# heaters-connectors.net
KiCad netlist of a schematic drawn in Altium Designer
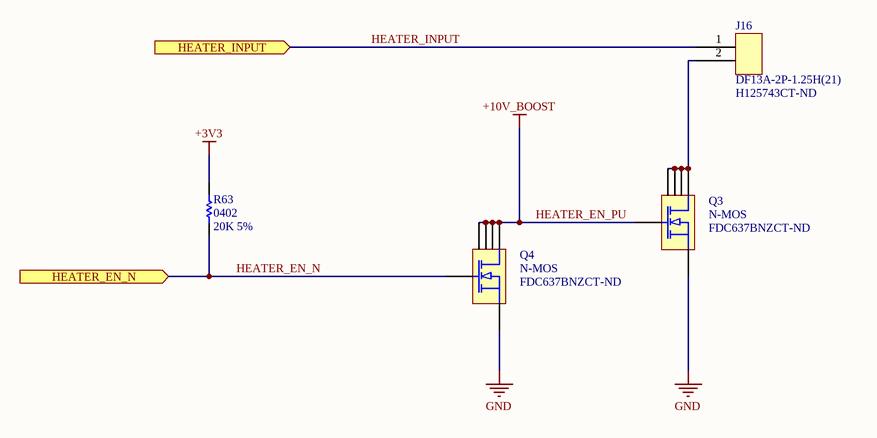
[diagram p0: heaters-connectors.SchDoc]

(export (version "E")
  (design (tool "Eeschema 10.0.6"))
  (components
    (comp (ref "J16")
      (value "DF13A-2P-1.25H(21)")
      (footprint "DF13A-2P-1.25H(21)")
      (description "2 pos DF13 right angle surface mount connector")
      (fields (field (name "SUPPLIER PART NUMBER 1") "H125743CT-ND"))
      (libsource (lib "DF13A-2P-1.25H(21)") (part "DF13A-2P-1.25H(21)"))
    )
    (comp (ref "Q3")
      (value "N-MOS")
      (footprint "SOT95P280X145-6N")
      (description "20V 6.2A, N-MOS, low gate on voltage")
      (fields (field (name "SUPPLIER PART NUMBER 1") "FDC637BNZCT-ND"))
      (libsource (lib "heron-general") (part "FDC637BNZCT-ND"))
    )
    (comp (ref "Q4")
      (value "N-MOS")
      (footprint "SOT95P280X145-6N")
      (description "20V 6.2A, N-MOS, low gate on voltage")
      (fields (field (name "SUPPLIER PART NUMBER 1") "FDC637BNZCT-ND"))
      (libsource (lib "heron-general") (part "FDC637BNZCT-ND"))
    )
    (comp (ref "R63")
      (value "0402")
      (footprint "RES0402R")
      (description "0402 resistor")
      (fields (field (name "ALTIUM_VALUE") "20K 5%"))
      (libsource (lib "RES0402") (part "RES0402"))
    )
  )
  (nets
    (net (code "1") (name "+3V3") (class "Default")
      (node (ref "R63") (pin "2") (pinfunction "2_2") (pintype "passive"))
    )
    (net (code "2") (name "+10V_BOOST") (class "Default")
      (node (ref "Q3") (pin "3") (pinfunction "G_3") (pintype "passive"))
      (node (ref "Q4") (pin "1") (pinfunction "D_1") (pintype "passive"))
      (node (ref "Q4") (pin "2") (pinfunction "D_2") (pintype "passive"))
      (node (ref "Q4") (pin "5") (pinfunction "D_5") (pintype "passive"))
      (node (ref "Q4") (pin "6") (pinfunction "D_6") (pintype "passive"))
    )
    (net (code "3") (name "/HEATER_EN_N") (class "Default")
      (node (ref "Q4") (pin "3") (pinfunction "G_3") (pintype "passive"))
      (node (ref "R63") (pin "1") (pinfunction "1_1") (pintype "passive"))
    )
    (net (code "4") (name "/HEATER_INPUT") (class "Default") (node (ref "J16") (pin "1") (pintype "passive")))
    (net (code "5") (name "GND") (class "Default")
      (node (ref "Q3") (pin "4") (pinfunction "S_4") (pintype "passive"))
      (node (ref "Q4") (pin "4") (pinfunction "S_4") (pintype "passive"))
    )
    (net (code "6") (name "Net-(J16-Pad2)") (class "Default")
      (node (ref "J16") (pin "2") (pintype "passive"))
      (node (ref "Q3") (pin "1") (pinfunction "D_1") (pintype "passive"))
      (node (ref "Q3") (pin "2") (pinfunction "D_2") (pintype "passive"))
      (node (ref "Q3") (pin "5") (pinfunction "D_5") (pintype "passive"))
      (node (ref "Q3") (pin "6") (pinfunction "D_6") (pintype "passive"))
    )
  )
)
